# obc-v2_CM4-SPI-UART.net
KiCad netlist of a schematic drawn in Altium Designer
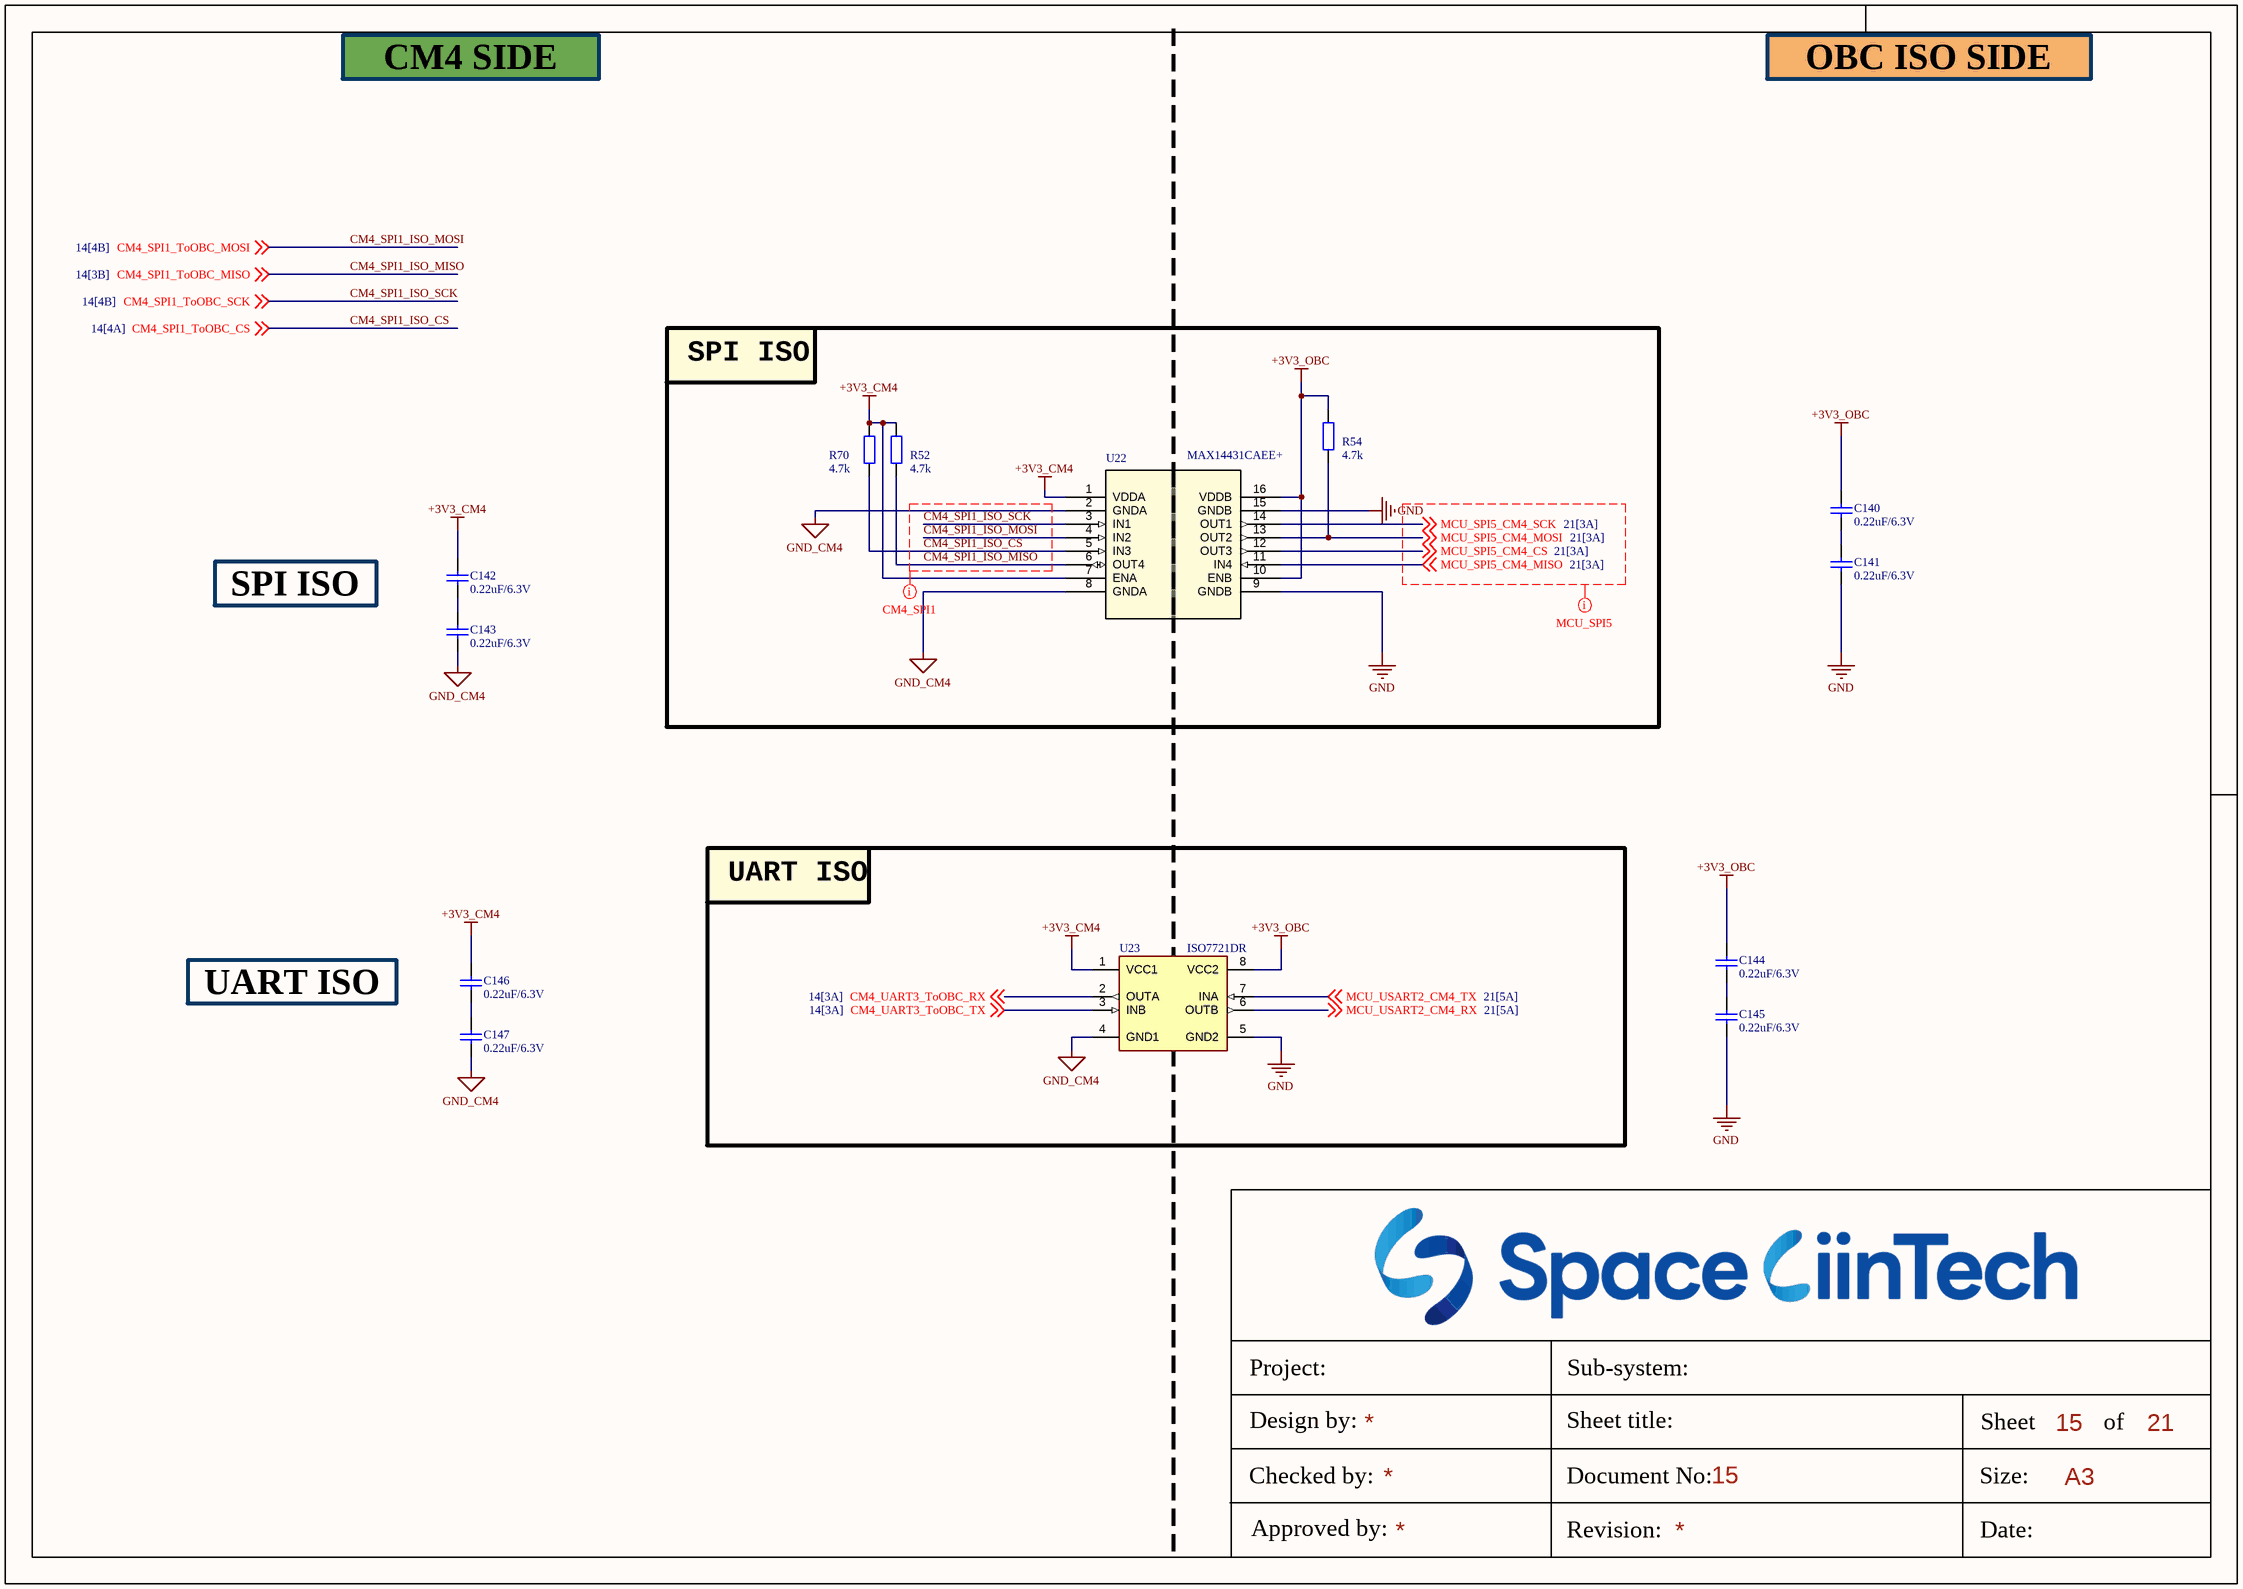
[diagram p0: obc-v2_CM4-SPI-UART.SchDoc]

(export (version "E")
  (design (tool "Eeschema 10.0.6"))
  (components
    (comp (ref "C140")
      (value "0.22uF/6.3V")
      (footprint "CAP_C_1005X60")
      (description "CAPC")
      (libsource (lib "Altium_Lib_by_KhueNguyenCreator") (part "Tu 0402 33nF 10V"))
    )
    (comp (ref "C141")
      (value "0.22uF/6.3V")
      (footprint "CAP_C_1005X60")
      (description "CAPC")
      (libsource (lib "Altium_Lib_by_KhueNguyenCreator") (part "Tu 0402 33nF 10V"))
    )
    (comp (ref "C142")
      (value "0.22uF/6.3V")
      (footprint "CAP_C_1005X60")
      (description "CAPC")
      (libsource (lib "Altium_Lib_by_KhueNguyenCreator") (part "Tu 0402 33nF 10V"))
    )
    (comp (ref "C143")
      (value "0.22uF/6.3V")
      (footprint "CAP_C_1005X60")
      (description "CAPC")
      (libsource (lib "Altium_Lib_by_KhueNguyenCreator") (part "Tu 0402 33nF 10V"))
    )
    (comp (ref "C144")
      (value "0.22uF/6.3V")
      (footprint "CAP_C_1005X60")
      (description "CAPC")
      (libsource (lib "Altium_Lib_by_KhueNguyenCreator") (part "Tu 0402 33nF 10V"))
    )
    (comp (ref "C145")
      (value "0.22uF/6.3V")
      (footprint "CAP_C_1005X60")
      (description "CAPC")
      (libsource (lib "Altium_Lib_by_KhueNguyenCreator") (part "Tu 0402 33nF 10V"))
    )
    (comp (ref "C146")
      (value "0.22uF/6.3V")
      (footprint "CAP_C_1005X60")
      (description "CAPC")
      (libsource (lib "Altium_Lib_by_KhueNguyenCreator") (part "Tu 0402 33nF 10V"))
    )
    (comp (ref "C147")
      (value "0.22uF/6.3V")
      (footprint "CAP_C_1005X60")
      (description "CAPC")
      (libsource (lib "Altium_Lib_by_KhueNguyenCreator") (part "Tu 0402 33nF 10V"))
    )
    (comp (ref "R52")
      (value "4.7k")
      (footprint "RES_C_1608X60")
      (description "RES")
      (libsource (lib "Altium_Lib_by_KhueNguyenCreator") (part "Tro 0603 1% 10k"))
    )
    (comp (ref "R54")
      (value "4.7k")
      (footprint "RES_C_1608X60")
      (description "RES")
      (libsource (lib "Altium_Lib_by_KhueNguyenCreator") (part "Tro 0603 1% 10k"))
    )
    (comp (ref "R70")
      (value "4.7k")
      (footprint "RES_C_1608X60")
      (description "RES")
      (libsource (lib "Altium_Lib_by_KhueNguyenCreator") (part "Tro 0603 1% 10k"))
    )
    (comp (ref "U22")
      (value "MAX14431CAEE+")
      (footprint "21-0055Q_E16MS+1F_MXM")
      (description "No Description Available")
      (libsource (lib "MAX14431CAEE&plus_") (part "MAX14431CAEE+"))
    )
    (comp (ref "U23")
      (value "ISO7721DR")
      (footprint "SOIC127P602X173-8N")
      (description "Robust EMC, dual-channel, 1/1, reinforced digital isolator 8-SOIC -55 to 125")
      (libsource (lib "ISO7721DR") (part "ISO7721DR"))
    )
  )
  (nets
    (net (code "1") (name "+3V3_CM4") (class "Default")
      (node (ref "C142") (pin "1") (pinfunction "1_1") (pintype "passive"))
      (node (ref "C146") (pin "1") (pinfunction "1_1") (pintype "passive"))
      (node (ref "R52") (pin "2") (pinfunction "2_2") (pintype "passive"))
      (node (ref "R70") (pin "2") (pinfunction "2_2") (pintype "passive"))
      (node (ref "U22") (pin "1") (pinfunction "VDDA_1") (pintype "power_in"))
      (node (ref "U22") (pin "7") (pinfunction "ENA_7") (pintype "passive"))
      (node (ref "U23") (pin "1") (pinfunction "VCC1_1") (pintype "power_in"))
    )
    (net (code "2") (name "+3V3_OBC") (class "Default")
      (node (ref "C140") (pin "2") (pinfunction "2_2") (pintype "passive"))
      (node (ref "C144") (pin "2") (pinfunction "2_2") (pintype "passive"))
      (node (ref "R54") (pin "2") (pinfunction "2_2") (pintype "passive"))
      (node (ref "U22") (pin "10") (pinfunction "ENB_10") (pintype "passive"))
      (node (ref "U22") (pin "16") (pinfunction "VDDB_16") (pintype "power_in"))
      (node (ref "U23") (pin "8") (pinfunction "VCC2_8") (pintype "power_in"))
    )
    (net (code "3") (name "CM4_SPI1_ToOBC_CS") (class "Default")
      (node (ref "R70") (pin "1") (pinfunction "1_1") (pintype "passive"))
      (node (ref "U22") (pin "5") (pinfunction "IN3_5") (pintype "input"))
    )
    (net (code "4") (name "CM4_SPI1_ToOBC_MISO") (class "Default")
      (node (ref "R52") (pin "1") (pinfunction "1_1") (pintype "passive"))
      (node (ref "U22") (pin "6") (pinfunction "OUT4_6") (pintype "bidirectional"))
    )
    (net (code "5") (name "CM4_SPI1_ToOBC_MOSI") (class "Default")
      (node (ref "U22") (pin "4") (pinfunction "IN2_4") (pintype "input"))
    )
    (net (code "6") (name "CM4_SPI1_ToOBC_SCK") (class "Default")
      (node (ref "U22") (pin "3") (pinfunction "IN1_3") (pintype "input"))
    )
    (net (code "7") (name "CM4_UART3_ToOBC_RX") (class "Default")
      (node (ref "U23") (pin "2") (pinfunction "OUTA_2") (pintype "output"))
    )
    (net (code "8") (name "CM4_UART3_ToOBC_TX") (class "Default")
      (node (ref "U23") (pin "3") (pinfunction "INB_3") (pintype "input"))
    )
    (net (code "9") (name "GND") (class "Default")
      (node (ref "C141") (pin "1") (pinfunction "1_1") (pintype "passive"))
      (node (ref "C145") (pin "1") (pinfunction "1_1") (pintype "passive"))
      (node (ref "U22") (pin "15") (pinfunction "GNDB_15") (pintype "power_in"))
      (node (ref "U22") (pin "9") (pinfunction "GNDB_9") (pintype "power_in"))
      (node (ref "U23") (pin "5") (pinfunction "GND2_5") (pintype "power_in"))
    )
    (net (code "10") (name "GND_CM4") (class "Default")
      (node (ref "C143") (pin "2") (pinfunction "2_2") (pintype "passive"))
      (node (ref "C147") (pin "2") (pinfunction "2_2") (pintype "passive"))
      (node (ref "U22") (pin "2") (pinfunction "GNDA_2") (pintype "power_in"))
      (node (ref "U22") (pin "8") (pinfunction "GNDA_8") (pintype "power_in"))
      (node (ref "U23") (pin "4") (pinfunction "GND1_4") (pintype "power_in"))
    )
    (net (code "11") (name "MCU_SPI5_CM4_CS") (class "Default")
      (node (ref "U22") (pin "12") (pinfunction "OUT3_12") (pintype "output"))
    )
    (net (code "12") (name "MCU_SPI5_CM4_MISO") (class "Default")
      (node (ref "U22") (pin "11") (pinfunction "IN4_11") (pintype "input"))
    )
    (net (code "13") (name "MCU_SPI5_CM4_MOSI") (class "Default")
      (node (ref "R54") (pin "1") (pinfunction "1_1") (pintype "passive"))
      (node (ref "U22") (pin "13") (pinfunction "OUT2_13") (pintype "output"))
    )
    (net (code "14") (name "MCU_SPI5_CM4_SCK") (class "Default")
      (node (ref "U22") (pin "14") (pinfunction "OUT1_14") (pintype "output"))
    )
    (net (code "15") (name "MCU_USART2_CM4_RX") (class "Default")
      (node (ref "U23") (pin "6") (pinfunction "OUTB_6") (pintype "output"))
    )
    (net (code "16") (name "MCU_USART2_CM4_TX") (class "Default")
      (node (ref "U23") (pin "7") (pinfunction "INA_7") (pintype "input"))
    )
    (net (code "17") (name "Net-(C140-Pad1)") (class "Default")
      (node (ref "C140") (pin "1") (pinfunction "1_1") (pintype "passive"))
      (node (ref "C141") (pin "2") (pinfunction "2_2") (pintype "passive"))
    )
    (net (code "18") (name "Net-(C142-Pad2)") (class "Default")
      (node (ref "C142") (pin "2") (pinfunction "2_2") (pintype "passive"))
      (node (ref "C143") (pin "1") (pinfunction "1_1") (pintype "passive"))
    )
    (net (code "19") (name "Net-(C144-Pad1)") (class "Default")
      (node (ref "C144") (pin "1") (pinfunction "1_1") (pintype "passive"))
      (node (ref "C145") (pin "2") (pinfunction "2_2") (pintype "passive"))
    )
    (net (code "20") (name "Net-(C146-Pad2)") (class "Default")
      (node (ref "C146") (pin "2") (pinfunction "2_2") (pintype "passive"))
      (node (ref "C147") (pin "1") (pinfunction "1_1") (pintype "passive"))
    )
  )
)
